# SensorBoard.net
KiCad netlist of a schematic drawn in EAGLE
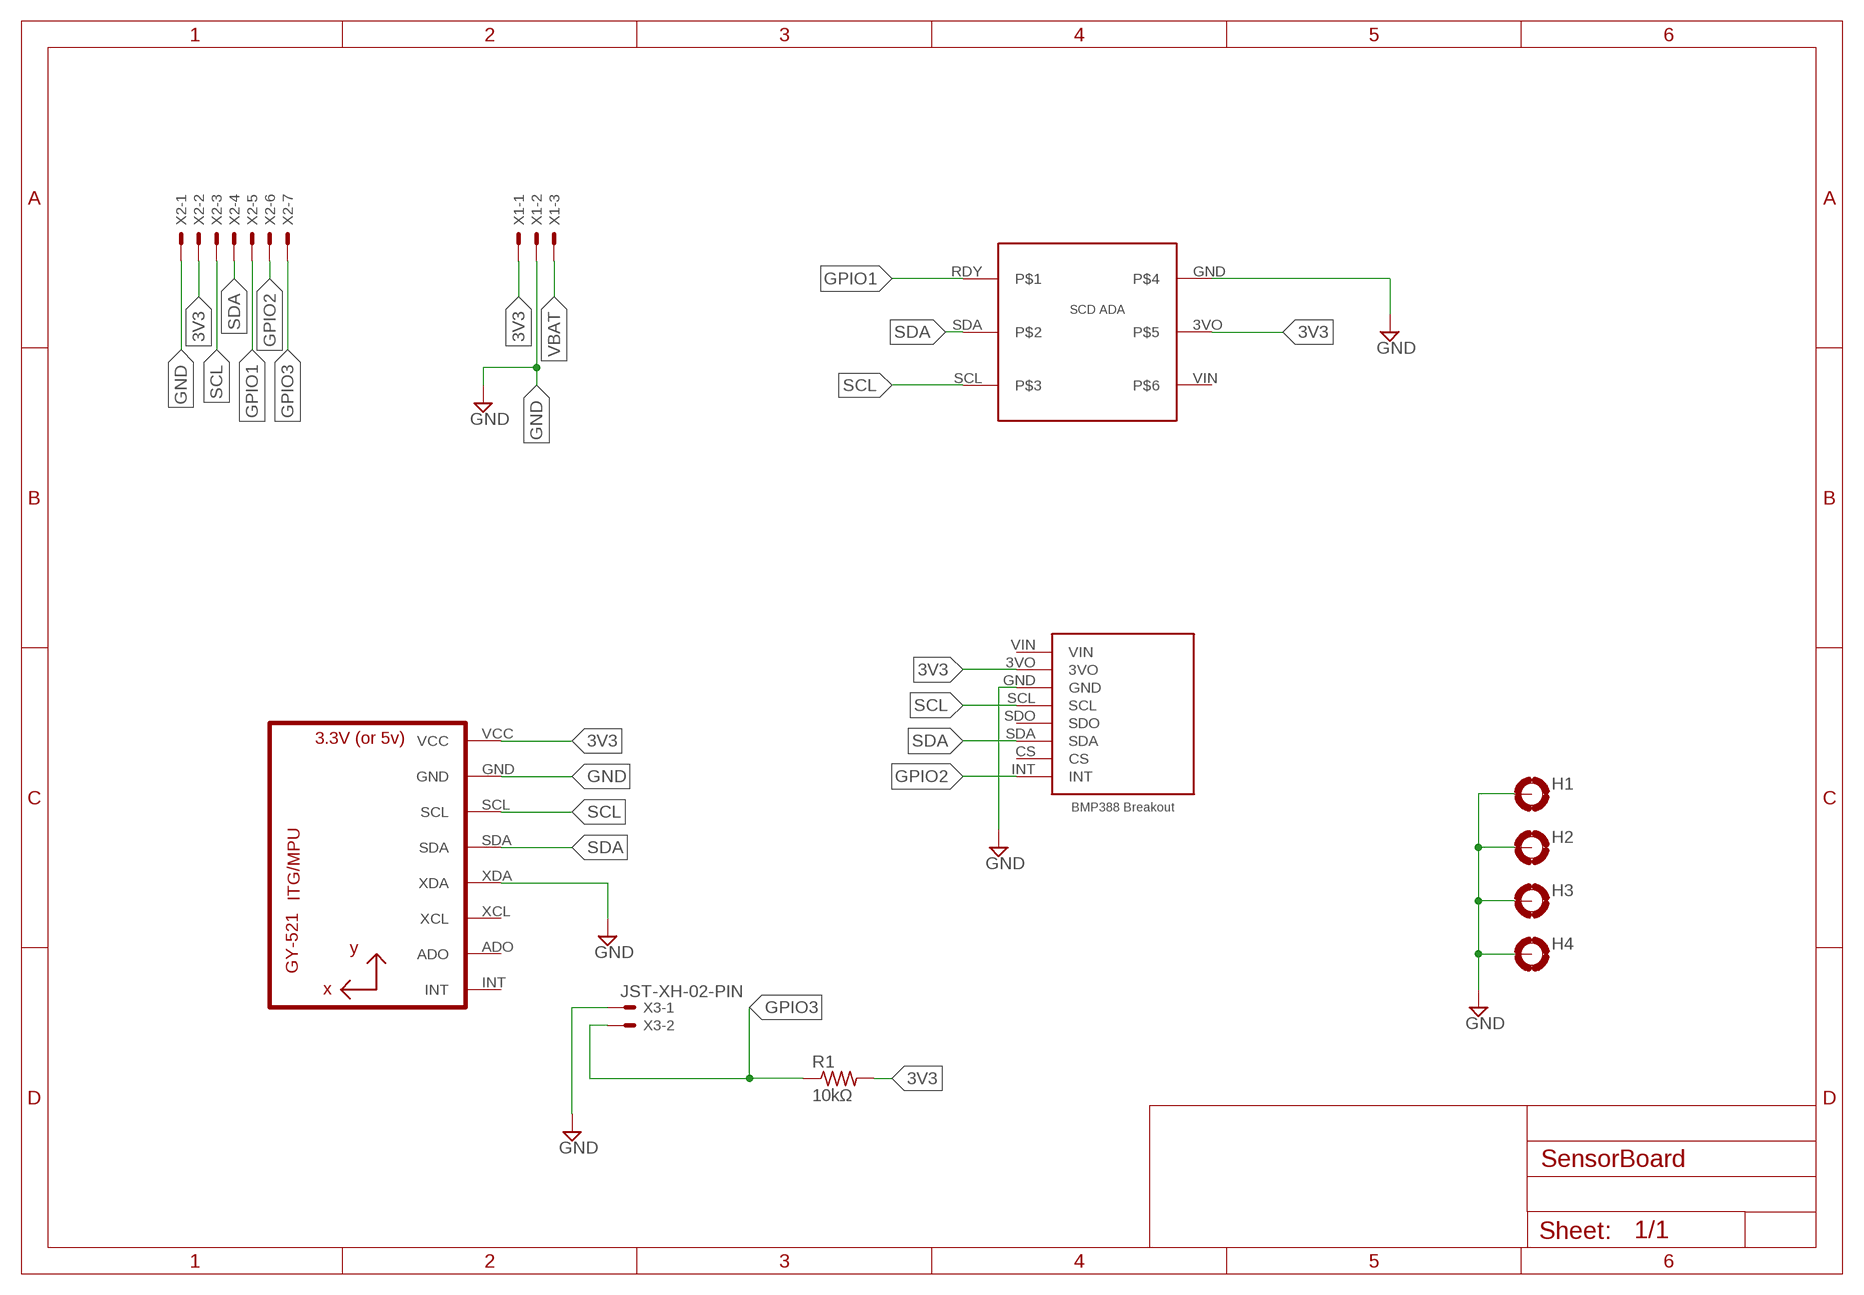
[diagram p0: schematic, sheet 1]

(export (version "E")
  (design (tool "Eeschema 10.0.6"))
  (components
    (comp (ref "H1")
      (value "MOUNT-PAD-ROUND3.0")
      (footprint "eagle-import:3,0-PAD")
      (libsource (lib "eagle-import") (part "MOUNT-PAD-ROUND3.0"))
    )
    (comp (ref "H2")
      (value "MOUNT-PAD-ROUND3.0")
      (footprint "eagle-import:3,0-PAD")
      (libsource (lib "eagle-import") (part "MOUNT-PAD-ROUND3.0"))
    )
    (comp (ref "H3")
      (value "MOUNT-PAD-ROUND3.0")
      (footprint "eagle-import:3,0-PAD")
      (libsource (lib "eagle-import") (part "MOUNT-PAD-ROUND3.0"))
    )
    (comp (ref "H4")
      (value "MOUNT-PAD-ROUND3.0")
      (footprint "eagle-import:3,0-PAD")
      (libsource (lib "eagle-import") (part "MOUNT-PAD-ROUND3.0"))
    )
    (comp (ref "R1")
      (value "10kΩ")
      (footprint "eagle-import:0204_7")
      (libsource (lib "eagle-import") (part "R-US_0204/7"))
    )
    (comp (ref "U$2")
      (value "BMP388BREAKOUT")
      (footprint "eagle-import:BMP388BREAKOUT")
      (libsource (lib "eagle-import") (part "BMP388BREAKOUT"))
    )
    (comp (ref "U$6")
      (value "SCD30_ADA")
      (footprint "eagle-import:SCD30_ADA")
      (libsource (lib "eagle-import") (part "SCD30_ADA"))
    )
    (comp (ref "U1")
      (value "GY-521MPU6050")
      (footprint "eagle-import:GY-521")
      (fields (field (name "MF") "GODREAM FORDREAM CO., LIMITED") (field (name "MP") "GY-521"))
      (libsource (lib "eagle-import") (part "GY-521MPU6050"))
    )
    (comp (ref "X1")
      (value "JST-XH-03-PIN")
      (footprint "eagle-import:JST-XH_S3B")
      (libsource (lib "eagle-import") (part "JST-XH-03-PIN"))
    )
    (comp (ref "X2")
      (value "JST-XH-07-PIN")
      (footprint "eagle-import:JST-XH_S7B")
      (libsource (lib "eagle-import") (part "JST-XH-07-PIN"))
    )
    (comp (ref "X3")
      (value "JST-XH-02-PIN")
      (footprint "eagle-import:JST-XH_S2B")
      (libsource (lib "eagle-import") (part "JST-XH-02-PIN"))
    )
  )
  (nets
    (net (code "1") (name "3V3") (class "Default")
      (node (ref "R1") (pin "2") (pinfunction "2_2") (pintype "passive"))
      (node (ref "U$2") (pin "3VO") (pinfunction "3VO_3VO") (pintype "bidirectional"))
      (node (ref "U$6") (pin "3VO") (pinfunction "P$5_3VO") (pintype "bidirectional"))
      (node (ref "U1") (pin "VCC") (pinfunction "VCC_VCC") (pintype "bidirectional"))
      (node (ref "X1") (pin "PIN1") (pinfunction "S_PIN1") (pintype "passive"))
      (node (ref "X2") (pin "PIN2") (pinfunction "S_PIN2") (pintype "passive"))
    )
    (net (code "2") (name "GND") (class "Default")
      (node (ref "H1") (pin "B3,0") (pinfunction "MOUNT_B3,0") (pintype "passive"))
      (node (ref "H2") (pin "B3,0") (pinfunction "MOUNT_B3,0") (pintype "passive"))
      (node (ref "H3") (pin "B3,0") (pinfunction "MOUNT_B3,0") (pintype "passive"))
      (node (ref "H4") (pin "B3,0") (pinfunction "MOUNT_B3,0") (pintype "passive"))
      (node (ref "U$2") (pin "GND") (pinfunction "GND_GND") (pintype "bidirectional"))
      (node (ref "U$6") (pin "GND") (pinfunction "P$4_GND") (pintype "bidirectional"))
      (node (ref "U1") (pin "GND") (pinfunction "GND_GND") (pintype "bidirectional"))
      (node (ref "U1") (pin "XDA") (pinfunction "XDA_XDA") (pintype "bidirectional"))
      (node (ref "X1") (pin "PIN2") (pinfunction "S_PIN2") (pintype "passive"))
      (node (ref "X2") (pin "PIN1") (pinfunction "S_PIN1") (pintype "passive"))
      (node (ref "X3") (pin "PIN1") (pinfunction "S_PIN1") (pintype "passive"))
    )
    (net (code "3") (name "GPIO1") (class "Default")
      (node (ref "U$6") (pin "RDY") (pinfunction "P$1_RDY") (pintype "bidirectional"))
      (node (ref "X2") (pin "PIN5") (pinfunction "S_PIN5") (pintype "passive"))
    )
    (net (code "4") (name "GPIO2") (class "Default")
      (node (ref "U$2") (pin "INT") (pinfunction "INT_INT") (pintype "bidirectional"))
      (node (ref "X2") (pin "PIN6") (pinfunction "S_PIN6") (pintype "passive"))
    )
    (net (code "5") (name "GPIO3") (class "Default")
      (node (ref "R1") (pin "1") (pinfunction "1_1") (pintype "passive"))
      (node (ref "X2") (pin "PIN7") (pinfunction "S_PIN7") (pintype "passive"))
      (node (ref "X3") (pin "PIN2") (pinfunction "S_PIN2") (pintype "passive"))
    )
    (net (code "6") (name "SCL") (class "Default")
      (node (ref "U$2") (pin "SCL") (pinfunction "SCL_SCL") (pintype "bidirectional"))
      (node (ref "U$6") (pin "SCL") (pinfunction "P$3_SCL") (pintype "bidirectional"))
      (node (ref "U1") (pin "SCL") (pinfunction "SCL_SCL") (pintype "bidirectional"))
      (node (ref "X2") (pin "PIN3") (pinfunction "S_PIN3") (pintype "passive"))
    )
    (net (code "7") (name "SDA") (class "Default")
      (node (ref "U$2") (pin "SDA") (pinfunction "SDA_SDA") (pintype "bidirectional"))
      (node (ref "U$6") (pin "SDA") (pinfunction "P$2_SDA") (pintype "bidirectional"))
      (node (ref "U1") (pin "SDA") (pinfunction "SDA_SDA") (pintype "bidirectional"))
      (node (ref "X2") (pin "PIN4") (pinfunction "S_PIN4") (pintype "passive"))
    )
    (net (code "8") (name "VBAT") (class "Default")
      (node (ref "X1") (pin "PIN3") (pinfunction "S_PIN3") (pintype "passive"))
    )
    (net (code "9") (name "unconnected-(U$2-PadCS)") (class "Default")
      (node (ref "U$2") (pin "CS") (pinfunction "CS_CS") (pintype "bidirectional"))
    )
    (net (code "10") (name "unconnected-(U$2-PadSDO)") (class "Default")
      (node (ref "U$2") (pin "SDO") (pinfunction "SDO_SDO") (pintype "bidirectional"))
    )
    (net (code "11") (name "unconnected-(U$2-PadVIN)") (class "Default")
      (node (ref "U$2") (pin "VIN") (pinfunction "VIN_VIN") (pintype "bidirectional"))
    )
    (net (code "12") (name "unconnected-(U$6-P$6-PadVIN)") (class "Default")
      (node (ref "U$6") (pin "VIN") (pinfunction "P$6_VIN") (pintype "bidirectional"))
    )
    (net (code "13") (name "unconnected-(U1-PadADO)") (class "Default")
      (node (ref "U1") (pin "ADO") (pinfunction "ADO_ADO") (pintype "bidirectional"))
    )
    (net (code "14") (name "unconnected-(U1-PadINT)") (class "Default")
      (node (ref "U1") (pin "INT") (pinfunction "INT_INT") (pintype "bidirectional"))
    )
    (net (code "15") (name "unconnected-(U1-PadXCL)") (class "Default")
      (node (ref "U1") (pin "XCL") (pinfunction "XCL_XCL") (pintype "bidirectional"))
    )
  )
)
